# mezza.net
KiCad netlist of a schematic drawn in Altium Designer
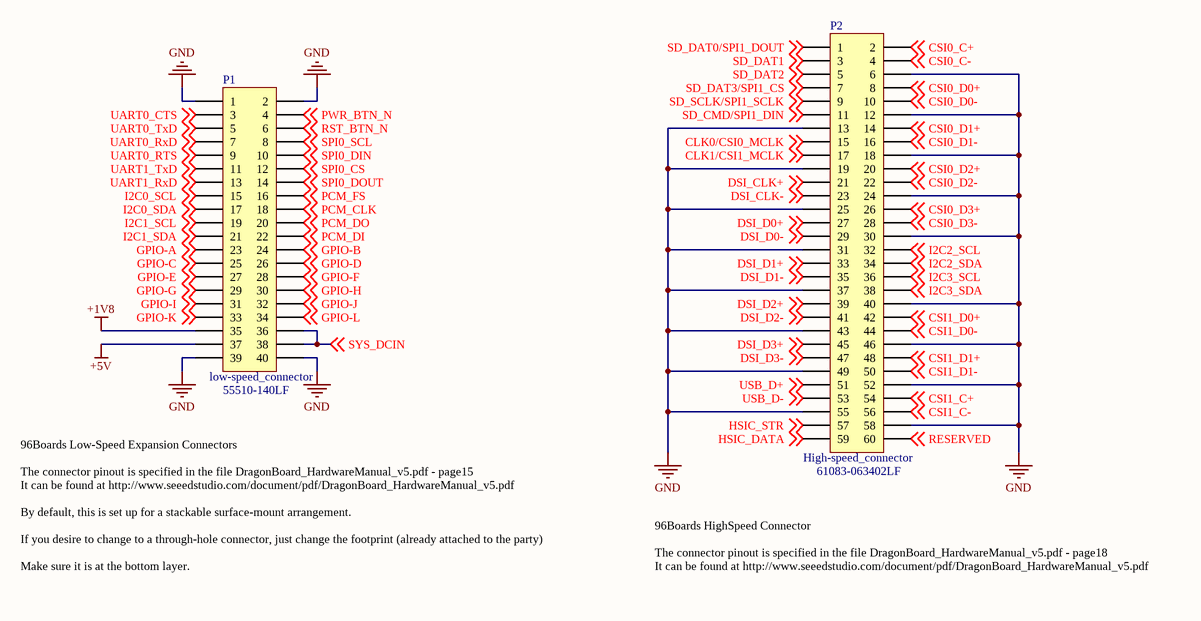
[diagram p0: mezza.SchDoc]

(export (version "E")
  (design (tool "Eeschema 10.0.6"))
  (components
    (comp (ref "P1")
      (value "low-speed_connector")
      (footprint "low-speed_connector_TH")
      (fields (field (name "PARTNUMBER") "55510-140LF"))
      (libsource (lib "mezza") (part "low-speed_connector"))
    )
    (comp (ref "P2")
      (value "High-speed_connector")
      (footprint "high-speed_connector")
      (fields (field (name "PARTNUMBER") "61083-063402LF"))
      (libsource (lib "mezza") (part "High-speed_connector"))
    )
  )
  (nets
    (net (code "1") (name "+1V8") (class "Default")
      (node (ref "P1") (pin "35") (pinfunction "35_35") (pintype "passive"))
    )
    (net (code "2") (name "+5V") (class "Default")
      (node (ref "P1") (pin "37") (pinfunction "37_37") (pintype "passive"))
    )
    (net (code "3") (name "CLK0{slash}CSI0_MCLK") (class "Default")
      (node (ref "P2") (pin "15") (pinfunction "15_15") (pintype "passive"))
    )
    (net (code "4") (name "CLK1{slash}CSI1_MCLK") (class "Default")
      (node (ref "P2") (pin "17") (pinfunction "17_17") (pintype "passive"))
    )
    (net (code "5") (name "CSI0_C+") (class "Default")
      (node (ref "P2") (pin "2") (pinfunction "2_2") (pintype "passive"))
    )
    (net (code "6") (name "CSI0_C-") (class "Default")
      (node (ref "P2") (pin "4") (pinfunction "4_4") (pintype "passive"))
    )
    (net (code "7") (name "CSI0_D0+") (class "Default")
      (node (ref "P2") (pin "8") (pinfunction "8_8") (pintype "passive"))
    )
    (net (code "8") (name "CSI0_D0-") (class "Default")
      (node (ref "P2") (pin "10") (pinfunction "10_10") (pintype "passive"))
    )
    (net (code "9") (name "CSI0_D1+") (class "Default")
      (node (ref "P2") (pin "14") (pinfunction "14_14") (pintype "passive"))
    )
    (net (code "10") (name "CSI0_D1-") (class "Default")
      (node (ref "P2") (pin "16") (pinfunction "16_16") (pintype "passive"))
    )
    (net (code "11") (name "CSI0_D2+") (class "Default")
      (node (ref "P2") (pin "20") (pinfunction "20_20") (pintype "passive"))
    )
    (net (code "12") (name "CSI0_D2-") (class "Default")
      (node (ref "P2") (pin "22") (pinfunction "22_22") (pintype "passive"))
    )
    (net (code "13") (name "CSI0_D3+") (class "Default")
      (node (ref "P2") (pin "26") (pinfunction "26_26") (pintype "passive"))
    )
    (net (code "14") (name "CSI0_D3-") (class "Default")
      (node (ref "P2") (pin "28") (pinfunction "28_28") (pintype "passive"))
    )
    (net (code "15") (name "CSI1_C+") (class "Default")
      (node (ref "P2") (pin "54") (pinfunction "54_54") (pintype "passive"))
    )
    (net (code "16") (name "CSI1_C-") (class "Default")
      (node (ref "P2") (pin "56") (pinfunction "56_56") (pintype "passive"))
    )
    (net (code "17") (name "CSI1_D0+") (class "Default")
      (node (ref "P2") (pin "42") (pinfunction "42_42") (pintype "passive"))
    )
    (net (code "18") (name "CSI1_D0-") (class "Default")
      (node (ref "P2") (pin "44") (pinfunction "44_44") (pintype "passive"))
    )
    (net (code "19") (name "CSI1_D1+") (class "Default")
      (node (ref "P2") (pin "48") (pinfunction "48_48") (pintype "passive"))
    )
    (net (code "20") (name "CSI1_D1-") (class "Default")
      (node (ref "P2") (pin "50") (pinfunction "50_50") (pintype "passive"))
    )
    (net (code "21") (name "DSI_CLK+") (class "Default")
      (node (ref "P2") (pin "21") (pinfunction "21_21") (pintype "passive"))
    )
    (net (code "22") (name "DSI_CLK-") (class "Default")
      (node (ref "P2") (pin "23") (pinfunction "23_23") (pintype "passive"))
    )
    (net (code "23") (name "DSI_D0+") (class "Default")
      (node (ref "P2") (pin "27") (pinfunction "27_27") (pintype "passive"))
    )
    (net (code "24") (name "DSI_D0-") (class "Default")
      (node (ref "P2") (pin "29") (pinfunction "29_29") (pintype "passive"))
    )
    (net (code "25") (name "DSI_D1+") (class "Default")
      (node (ref "P2") (pin "33") (pinfunction "33_33") (pintype "passive"))
    )
    (net (code "26") (name "DSI_D1-") (class "Default")
      (node (ref "P2") (pin "35") (pinfunction "35_35") (pintype "passive"))
    )
    (net (code "27") (name "DSI_D2+") (class "Default")
      (node (ref "P2") (pin "39") (pinfunction "39_39") (pintype "passive"))
    )
    (net (code "28") (name "DSI_D2-") (class "Default")
      (node (ref "P2") (pin "41") (pinfunction "41_41") (pintype "passive"))
    )
    (net (code "29") (name "DSI_D3+") (class "Default")
      (node (ref "P2") (pin "45") (pinfunction "45_45") (pintype "passive"))
    )
    (net (code "30") (name "DSI_D3-") (class "Default")
      (node (ref "P2") (pin "47") (pinfunction "47_47") (pintype "passive"))
    )
    (net (code "31") (name "GND") (class "Default")
      (node (ref "P1") (pin "1") (pinfunction "1_1") (pintype "passive"))
      (node (ref "P1") (pin "2") (pinfunction "2_2") (pintype "passive"))
      (node (ref "P1") (pin "39") (pinfunction "39_39") (pintype "passive"))
      (node (ref "P1") (pin "40") (pinfunction "40_40") (pintype "passive"))
      (node (ref "P2") (pin "12") (pinfunction "12_12") (pintype "passive"))
      (node (ref "P2") (pin "13") (pinfunction "13_13") (pintype "passive"))
      (node (ref "P2") (pin "18") (pinfunction "18_18") (pintype "passive"))
      (node (ref "P2") (pin "19") (pinfunction "19_19") (pintype "passive"))
      (node (ref "P2") (pin "24") (pinfunction "24_24") (pintype "passive"))
      (node (ref "P2") (pin "25") (pinfunction "25_25") (pintype "passive"))
      (node (ref "P2") (pin "30") (pinfunction "30_30") (pintype "passive"))
      (node (ref "P2") (pin "31") (pinfunction "31_31") (pintype "passive"))
      (node (ref "P2") (pin "37") (pinfunction "37_37") (pintype "passive"))
      (node (ref "P2") (pin "40") (pinfunction "40_40") (pintype "passive"))
      (node (ref "P2") (pin "43") (pinfunction "43_43") (pintype "passive"))
      (node (ref "P2") (pin "46") (pinfunction "46_46") (pintype "passive"))
      (node (ref "P2") (pin "49") (pinfunction "49_49") (pintype "passive"))
      (node (ref "P2") (pin "52") (pinfunction "52_52") (pintype "passive"))
      (node (ref "P2") (pin "55") (pinfunction "55_55") (pintype "passive"))
      (node (ref "P2") (pin "58") (pinfunction "58_58") (pintype "passive"))
      (node (ref "P2") (pin "6") (pinfunction "6_6") (pintype "passive"))
    )
    (net (code "32") (name "GPIO-A") (class "Default")
      (node (ref "P1") (pin "23") (pinfunction "23_23") (pintype "passive"))
    )
    (net (code "33") (name "GPIO-B") (class "Default")
      (node (ref "P1") (pin "24") (pinfunction "24_24") (pintype "passive"))
    )
    (net (code "34") (name "GPIO-C") (class "Default")
      (node (ref "P1") (pin "25") (pinfunction "25_25") (pintype "passive"))
    )
    (net (code "35") (name "GPIO-D") (class "Default")
      (node (ref "P1") (pin "26") (pinfunction "26_26") (pintype "passive"))
    )
    (net (code "36") (name "GPIO-E") (class "Default")
      (node (ref "P1") (pin "27") (pinfunction "27_27") (pintype "passive"))
    )
    (net (code "37") (name "GPIO-F") (class "Default")
      (node (ref "P1") (pin "28") (pinfunction "28_28") (pintype "passive"))
    )
    (net (code "38") (name "GPIO-G") (class "Default")
      (node (ref "P1") (pin "29") (pinfunction "29_29") (pintype "passive"))
    )
    (net (code "39") (name "GPIO-H") (class "Default")
      (node (ref "P1") (pin "30") (pinfunction "30_30") (pintype "passive"))
    )
    (net (code "40") (name "GPIO-I") (class "Default")
      (node (ref "P1") (pin "31") (pinfunction "31_31") (pintype "passive"))
    )
    (net (code "41") (name "GPIO-J") (class "Default")
      (node (ref "P1") (pin "32") (pinfunction "32_32") (pintype "passive"))
    )
    (net (code "42") (name "GPIO-K") (class "Default")
      (node (ref "P1") (pin "33") (pinfunction "33_33") (pintype "passive"))
    )
    (net (code "43") (name "GPIO-L") (class "Default")
      (node (ref "P1") (pin "34") (pinfunction "34_34") (pintype "passive"))
    )
    (net (code "44") (name "HSIC_DATA") (class "Default")
      (node (ref "P2") (pin "59") (pinfunction "59_59") (pintype "passive"))
    )
    (net (code "45") (name "HSIC_STR") (class "Default")
      (node (ref "P2") (pin "39") (pinfunction "57_39") (pintype "passive"))
    )
    (net (code "46") (name "I2C0_SCL") (class "Default")
      (node (ref "P1") (pin "15") (pinfunction "15_15") (pintype "passive"))
    )
    (net (code "47") (name "I2C0_SDA") (class "Default")
      (node (ref "P1") (pin "17") (pinfunction "17_17") (pintype "passive"))
    )
    (net (code "48") (name "I2C1_SCL") (class "Default")
      (node (ref "P1") (pin "19") (pinfunction "19_19") (pintype "passive"))
    )
    (net (code "49") (name "I2C1_SDA") (class "Default")
      (node (ref "P1") (pin "21") (pinfunction "21_21") (pintype "passive"))
    )
    (net (code "50") (name "I2C2_SCL") (class "Default")
      (node (ref "P2") (pin "32") (pinfunction "32_32") (pintype "passive"))
    )
    (net (code "51") (name "I2C2_SDA") (class "Default")
      (node (ref "P2") (pin "34") (pinfunction "34_34") (pintype "passive"))
    )
    (net (code "52") (name "I2C3_SCL") (class "Default")
      (node (ref "P2") (pin "36") (pinfunction "36_36") (pintype "passive"))
    )
    (net (code "53") (name "I2C3_SDA") (class "Default")
      (node (ref "P2") (pin "38") (pinfunction "38_38") (pintype "passive"))
    )
    (net (code "54") (name "PCM_CLK") (class "Default")
      (node (ref "P1") (pin "18") (pinfunction "18_18") (pintype "passive"))
    )
    (net (code "55") (name "PCM_DI") (class "Default")
      (node (ref "P1") (pin "22") (pinfunction "22_22") (pintype "passive"))
    )
    (net (code "56") (name "PCM_DO") (class "Default")
      (node (ref "P1") (pin "20") (pinfunction "20_20") (pintype "passive"))
    )
    (net (code "57") (name "PCM_FS") (class "Default")
      (node (ref "P1") (pin "16") (pinfunction "16_16") (pintype "passive"))
    )
    (net (code "58") (name "PWR_BTN_N") (class "Default")
      (node (ref "P1") (pin "4") (pinfunction "4_4") (pintype "passive"))
    )
    (net (code "59") (name "RESERVED") (class "Default")
      (node (ref "P2") (pin "38") (pinfunction "60_38") (pintype "passive"))
    )
    (net (code "60") (name "RST_BTN_N") (class "Default")
      (node (ref "P1") (pin "6") (pinfunction "6_6") (pintype "passive"))
    )
    (net (code "61") (name "SD_CMD{slash}SPI1_DIN") (class "Default")
      (node (ref "P2") (pin "11") (pinfunction "11_11") (pintype "passive"))
    )
    (net (code "62") (name "SD_DAT0{slash}SPI1_DOUT") (class "Default")
      (node (ref "P2") (pin "1") (pinfunction "1_1") (pintype "passive"))
    )
    (net (code "63") (name "SD_DAT1") (class "Default")
      (node (ref "P2") (pin "3") (pinfunction "3_3") (pintype "passive"))
    )
    (net (code "64") (name "SD_DAT2") (class "Default")
      (node (ref "P2") (pin "5") (pinfunction "5_5") (pintype "passive"))
    )
    (net (code "65") (name "SD_DAT3{slash}SPI1_CS") (class "Default")
      (node (ref "P2") (pin "7") (pinfunction "7_7") (pintype "passive"))
    )
    (net (code "66") (name "SD_SCLK{slash}SPI1_SCLK") (class "Default")
      (node (ref "P2") (pin "9") (pinfunction "9_9") (pintype "passive"))
    )
    (net (code "67") (name "SPI0_CS") (class "Default")
      (node (ref "P1") (pin "12") (pinfunction "12_12") (pintype "passive"))
    )
    (net (code "68") (name "SPI0_DIN") (class "Default")
      (node (ref "P1") (pin "10") (pinfunction "10_10") (pintype "passive"))
    )
    (net (code "69") (name "SPI0_DOUT") (class "Default")
      (node (ref "P1") (pin "14") (pinfunction "14_14") (pintype "passive"))
    )
    (net (code "70") (name "SPI0_SCL") (class "Default")
      (node (ref "P1") (pin "8") (pinfunction "8_8") (pintype "passive"))
    )
    (net (code "71") (name "SYS_DCIN") (class "Default")
      (node (ref "P1") (pin "36") (pinfunction "36_36") (pintype "passive"))
      (node (ref "P1") (pin "38") (pinfunction "38_38") (pintype "passive"))
    )
    (net (code "72") (name "UART0_CTS") (class "Default")
      (node (ref "P1") (pin "3") (pinfunction "3_3") (pintype "passive"))
    )
    (net (code "73") (name "UART0_RTS") (class "Default")
      (node (ref "P1") (pin "9") (pinfunction "9_9") (pintype "passive"))
    )
    (net (code "74") (name "UART0_RxD") (class "Default")
      (node (ref "P1") (pin "7") (pinfunction "7_7") (pintype "passive"))
    )
    (net (code "75") (name "UART0_TxD") (class "Default")
      (node (ref "P1") (pin "5") (pinfunction "5_5") (pintype "passive"))
    )
    (net (code "76") (name "UART1_RxD") (class "Default")
      (node (ref "P1") (pin "13") (pinfunction "13_13") (pintype "passive"))
    )
    (net (code "77") (name "UART1_TxD") (class "Default")
      (node (ref "P1") (pin "11") (pinfunction "11_11") (pintype "passive"))
    )
    (net (code "78") (name "USB_D+") (class "Default")
      (node (ref "P2") (pin "51") (pinfunction "51_51") (pintype "passive"))
    )
    (net (code "79") (name "USB_D-") (class "Default")
      (node (ref "P2") (pin "53") (pinfunction "53_53") (pintype "passive"))
    )
  )
)
